# L293D.net
KiCad netlist of a schematic drawn in EAGLE
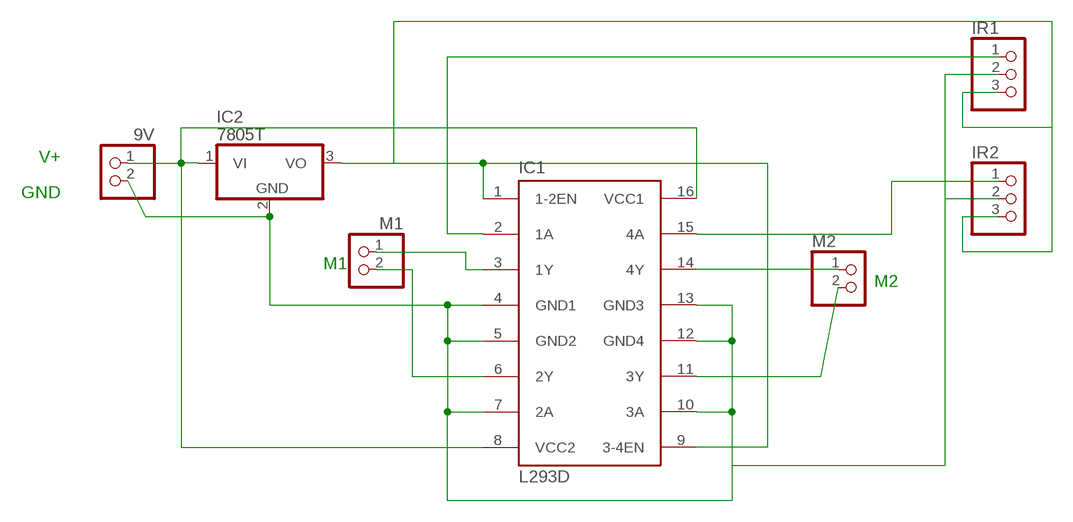
[diagram p0: schematic, sheet 1]

(export (version "E")
  (design (tool "Eeschema 10.0.6"))
  (components
    (comp (ref "9V")
      (value "PINHD-1X2")
      (footprint "eagle-import:1X02")
      (libsource (lib "eagle-import") (part "PINHD-1X2"))
    )
    (comp (ref "IC1")
      (value "L293D")
      (footprint "eagle-import:DIL16")
      (libsource (lib "eagle-import") (part "L293D"))
    )
    (comp (ref "IC2")
      (value "7805T")
      (footprint "eagle-import:TO220H")
      (libsource (lib "eagle-import") (part "78T05"))
    )
    (comp (ref "IR1")
      (value "PINHD-1X3")
      (footprint "eagle-import:1X03")
      (libsource (lib "eagle-import") (part "PINHD-1X3"))
    )
    (comp (ref "IR2")
      (value "PINHD-1X3")
      (footprint "eagle-import:1X03")
      (libsource (lib "eagle-import") (part "PINHD-1X3"))
    )
    (comp (ref "M1")
      (value "PINHD-1X2")
      (footprint "eagle-import:1X02")
      (libsource (lib "eagle-import") (part "PINHD-1X2"))
    )
    (comp (ref "M2")
      (value "PINHD-1X2")
      (footprint "eagle-import:1X02")
      (libsource (lib "eagle-import") (part "PINHD-1X2"))
    )
  )
  (nets
    (net (code "1") (name "Net-(IC1-1-2EN)") (class "Default")
      (node (ref "IC1") (pin "1") (pinfunction "1-2EN_1") (pintype "input"))
      (node (ref "IC1") (pin "9") (pinfunction "3-4EN_9") (pintype "input"))
      (node (ref "IC2") (pin "3") (pinfunction "VO_3") (pintype "passive"))
      (node (ref "IR1") (pin "3") (pinfunction "3_3") (pintype "passive"))
      (node (ref "IR2") (pin "3") (pinfunction "3_3") (pintype "passive"))
    )
    (net (code "2") (name "Net-(IC1-1A)") (class "Default")
      (node (ref "IC1") (pin "2") (pinfunction "1A_2") (pintype "input"))
      (node (ref "IR1") (pin "1") (pinfunction "1_1") (pintype "passive"))
    )
    (net (code "3") (name "Net-(IC1-1Y)") (class "Default")
      (node (ref "IC1") (pin "3") (pinfunction "1Y_3") (pintype "output"))
      (node (ref "M1") (pin "1") (pinfunction "1_1") (pintype "passive"))
    )
    (net (code "4") (name "Net-(IC1-2A)") (class "Default")
      (node (ref "9V") (pin "2") (pinfunction "2_2") (pintype "passive"))
      (node (ref "IC1") (pin "10") (pinfunction "3A_10") (pintype "input"))
      (node (ref "IC1") (pin "12") (pinfunction "GND4_12") (pintype "power_in"))
      (node (ref "IC1") (pin "13") (pinfunction "GND3_13") (pintype "power_in"))
      (node (ref "IC1") (pin "4") (pinfunction "GND1_4") (pintype "power_in"))
      (node (ref "IC1") (pin "5") (pinfunction "GND2_5") (pintype "power_in"))
      (node (ref "IC1") (pin "7") (pinfunction "2A_7") (pintype "input"))
      (node (ref "IC2") (pin "2") (pinfunction "GND_2") (pintype "passive"))
      (node (ref "IR1") (pin "2") (pinfunction "2_2") (pintype "passive"))
      (node (ref "IR2") (pin "2") (pinfunction "2_2") (pintype "passive"))
    )
    (net (code "5") (name "Net-(IC1-2Y)") (class "Default")
      (node (ref "IC1") (pin "6") (pinfunction "2Y_6") (pintype "output"))
      (node (ref "M1") (pin "2") (pinfunction "2_2") (pintype "passive"))
    )
    (net (code "6") (name "Net-(IC1-3Y)") (class "Default")
      (node (ref "IC1") (pin "11") (pinfunction "3Y_11") (pintype "output"))
      (node (ref "M2") (pin "2") (pinfunction "2_2") (pintype "passive"))
    )
    (net (code "7") (name "Net-(IC1-4A)") (class "Default")
      (node (ref "IC1") (pin "15") (pinfunction "4A_15") (pintype "input"))
      (node (ref "IR2") (pin "1") (pinfunction "1_1") (pintype "passive"))
    )
    (net (code "8") (name "Net-(IC1-4Y)") (class "Default")
      (node (ref "IC1") (pin "14") (pinfunction "4Y_14") (pintype "output"))
      (node (ref "M2") (pin "1") (pinfunction "1_1") (pintype "passive"))
    )
    (net (code "9") (name "Net-(IC1-VCC1)") (class "Default")
      (node (ref "9V") (pin "1") (pinfunction "1_1") (pintype "passive"))
      (node (ref "IC1") (pin "16") (pinfunction "VCC1_16") (pintype "power_in"))
      (node (ref "IC1") (pin "8") (pinfunction "VCC2_8") (pintype "power_in"))
      (node (ref "IC2") (pin "1") (pinfunction "VI_1") (pintype "input"))
    )
  )
)
